# ICS40300-Silicon-Mic_Rev-A.net
KiCad netlist of a schematic drawn in EAGLE
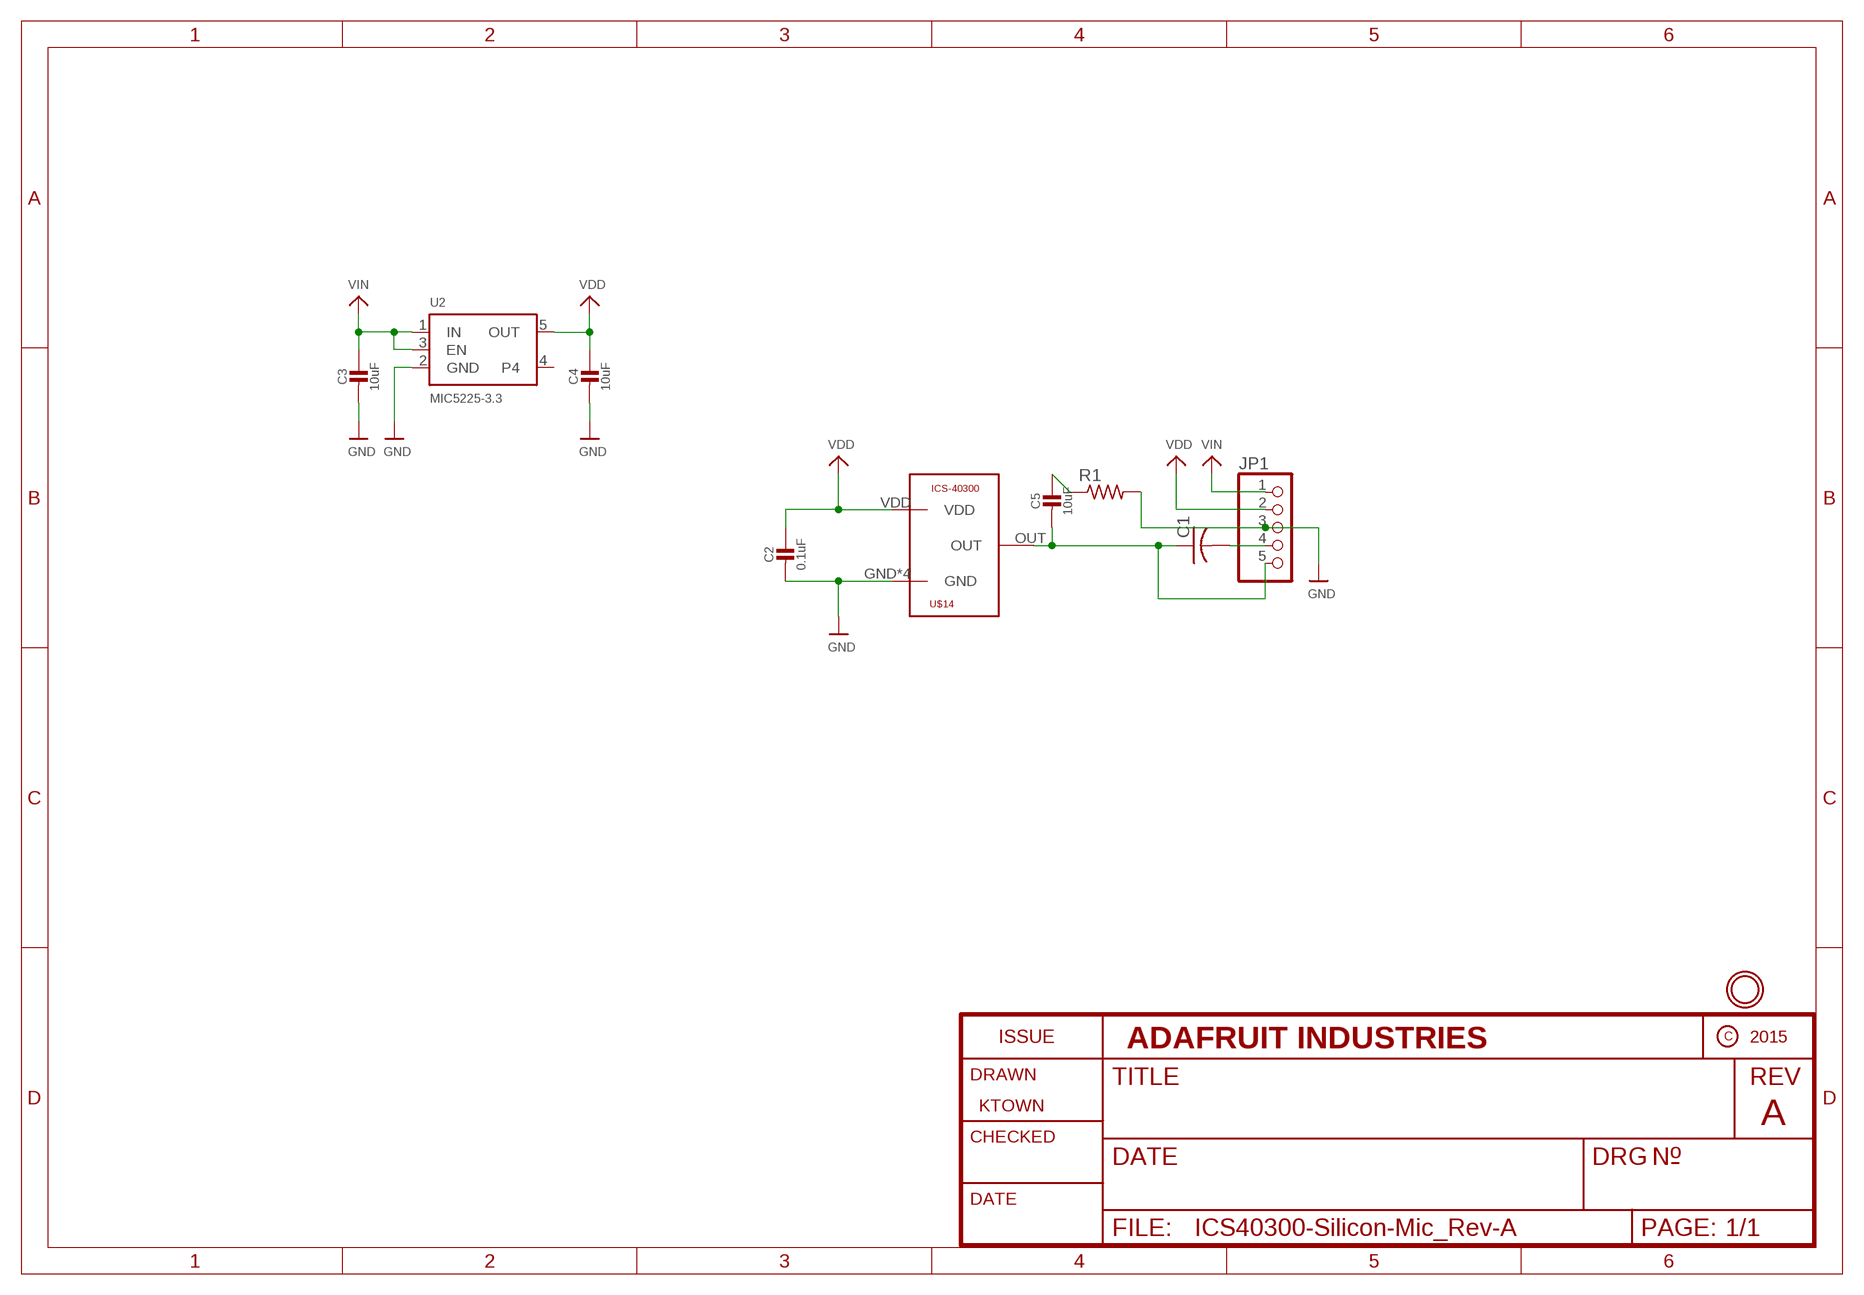
[diagram p0: schematic, sheet 1]

(export (version "E")
  (design (tool "Eeschema 10.0.6"))
  (components
    (comp (ref "C1")
      (value "C-USC3216")
      (footprint "eagle-import:C3216")
      (libsource (lib "eagle-import") (part "C-USC3216"))
    )
    (comp (ref "C2")
      (value "0.1uF")
      (footprint "eagle-import:0805-NO")
      (libsource (lib "eagle-import") (part "CAP_CERAMIC0805-NOOUTLINE"))
    )
    (comp (ref "C3")
      (value "10uF")
      (footprint "eagle-import:0805-NO")
      (libsource (lib "eagle-import") (part "CAP_CERAMIC0805-NOOUTLINE"))
    )
    (comp (ref "C4")
      (value "10uF")
      (footprint "eagle-import:0805-NO")
      (libsource (lib "eagle-import") (part "CAP_CERAMIC0805-NOOUTLINE"))
    )
    (comp (ref "C5")
      (value "10uF")
      (footprint "eagle-import:0805-NO")
      (libsource (lib "eagle-import") (part "CAP_CERAMIC0805-NOOUTLINE"))
    )
    (comp (ref "JP1")
      (value "HEADER-1X576MIL")
      (footprint "eagle-import:1X05_ROUND_76")
      (libsource (lib "eagle-import") (part "HEADER-1X576MIL"))
    )
    (comp (ref "R1")
      (value "R-US_M0805")
      (footprint "eagle-import:M0805")
      (libsource (lib "eagle-import") (part "R-US_M0805"))
    )
    (comp (ref "U$12")
      (value "MOUNTINGHOLE2.5")
      (footprint "eagle-import:MOUNTINGHOLE_2.5_PLATED")
      (libsource (lib "eagle-import") (part "MOUNTINGHOLE2.5"))
    )
    (comp (ref "U$14")
      (value "ICS-40300")
      (footprint "eagle-import:ICS-40300")
      (libsource (lib "eagle-import") (part "ICS-40300"))
    )
    (comp (ref "U2")
      (value "MIC5225-3.3")
      (footprint "eagle-import:SOT23-5")
      (libsource (lib "eagle-import") (part "VREG_SOT23-5"))
    )
  )
  (nets
    (net (code "1") (name "GND") (class "Default")
      (node (ref "C2") (pin "2") (pinfunction "2_2") (pintype "passive"))
      (node (ref "C3") (pin "2") (pinfunction "2_2") (pintype "passive"))
      (node (ref "C4") (pin "2") (pinfunction "2_2") (pintype "passive"))
      (node (ref "JP1") (pin "3") (pinfunction "3_3") (pintype "passive"))
      (node (ref "R1") (pin "2") (pinfunction "2_2") (pintype "passive"))
      (node (ref "U$14") (pin "GND") (pinfunction "GND_GND") (pintype "bidirectional"))
      (node (ref "U$14") (pin "GND1") (pinfunction "GND_GND1") (pintype "bidirectional"))
      (node (ref "U$14") (pin "GND2") (pinfunction "GND_GND2") (pintype "bidirectional"))
      (node (ref "U$14") (pin "GND3") (pinfunction "GND_GND3") (pintype "bidirectional"))
      (node (ref "U2") (pin "2") (pinfunction "GND_2") (pintype "power_in"))
    )
    (net (code "2") (name "Net-(C1-Pad1)") (class "Default")
      (node (ref "C1") (pin "1") (pinfunction "1_1") (pintype "passive"))
      (node (ref "C5") (pin "2") (pinfunction "2_2") (pintype "passive"))
      (node (ref "JP1") (pin "5") (pinfunction "5_5") (pintype "passive"))
      (node (ref "U$14") (pin "OUT") (pinfunction "OUT_OUT") (pintype "bidirectional"))
    )
    (net (code "3") (name "Net-(C1-Pad2)") (class "Default")
      (node (ref "C1") (pin "2") (pinfunction "2_2") (pintype "passive"))
      (node (ref "JP1") (pin "4") (pinfunction "4_4") (pintype "passive"))
    )
    (net (code "4") (name "Net-(C5-Pad1)") (class "Default")
      (node (ref "C5") (pin "1") (pinfunction "1_1") (pintype "passive"))
      (node (ref "R1") (pin "1") (pinfunction "1_1") (pintype "passive"))
    )
    (net (code "5") (name "VDD") (class "Default")
      (node (ref "C2") (pin "1") (pinfunction "1_1") (pintype "passive"))
      (node (ref "C4") (pin "1") (pinfunction "1_1") (pintype "passive"))
      (node (ref "JP1") (pin "2") (pinfunction "2_2") (pintype "passive"))
      (node (ref "U$14") (pin "VDD") (pinfunction "VDD_VDD") (pintype "bidirectional"))
      (node (ref "U2") (pin "5") (pinfunction "OUT_5") (pintype "power_in"))
    )
    (net (code "6") (name "VIN") (class "Default")
      (node (ref "C3") (pin "1") (pinfunction "1_1") (pintype "passive"))
      (node (ref "JP1") (pin "1") (pinfunction "1_1") (pintype "passive"))
      (node (ref "U2") (pin "1") (pinfunction "IN_1") (pintype "power_in"))
      (node (ref "U2") (pin "3") (pinfunction "EN_3") (pintype "input"))
    )
    (net (code "7") (name "unconnected-(U2-P4-Pad4)") (class "Default")
      (node (ref "U2") (pin "4") (pinfunction "P4_4") (pintype "bidirectional"))
    )
  )
)
